# EndEffector.net
KiCad netlist of a schematic drawn in EAGLE
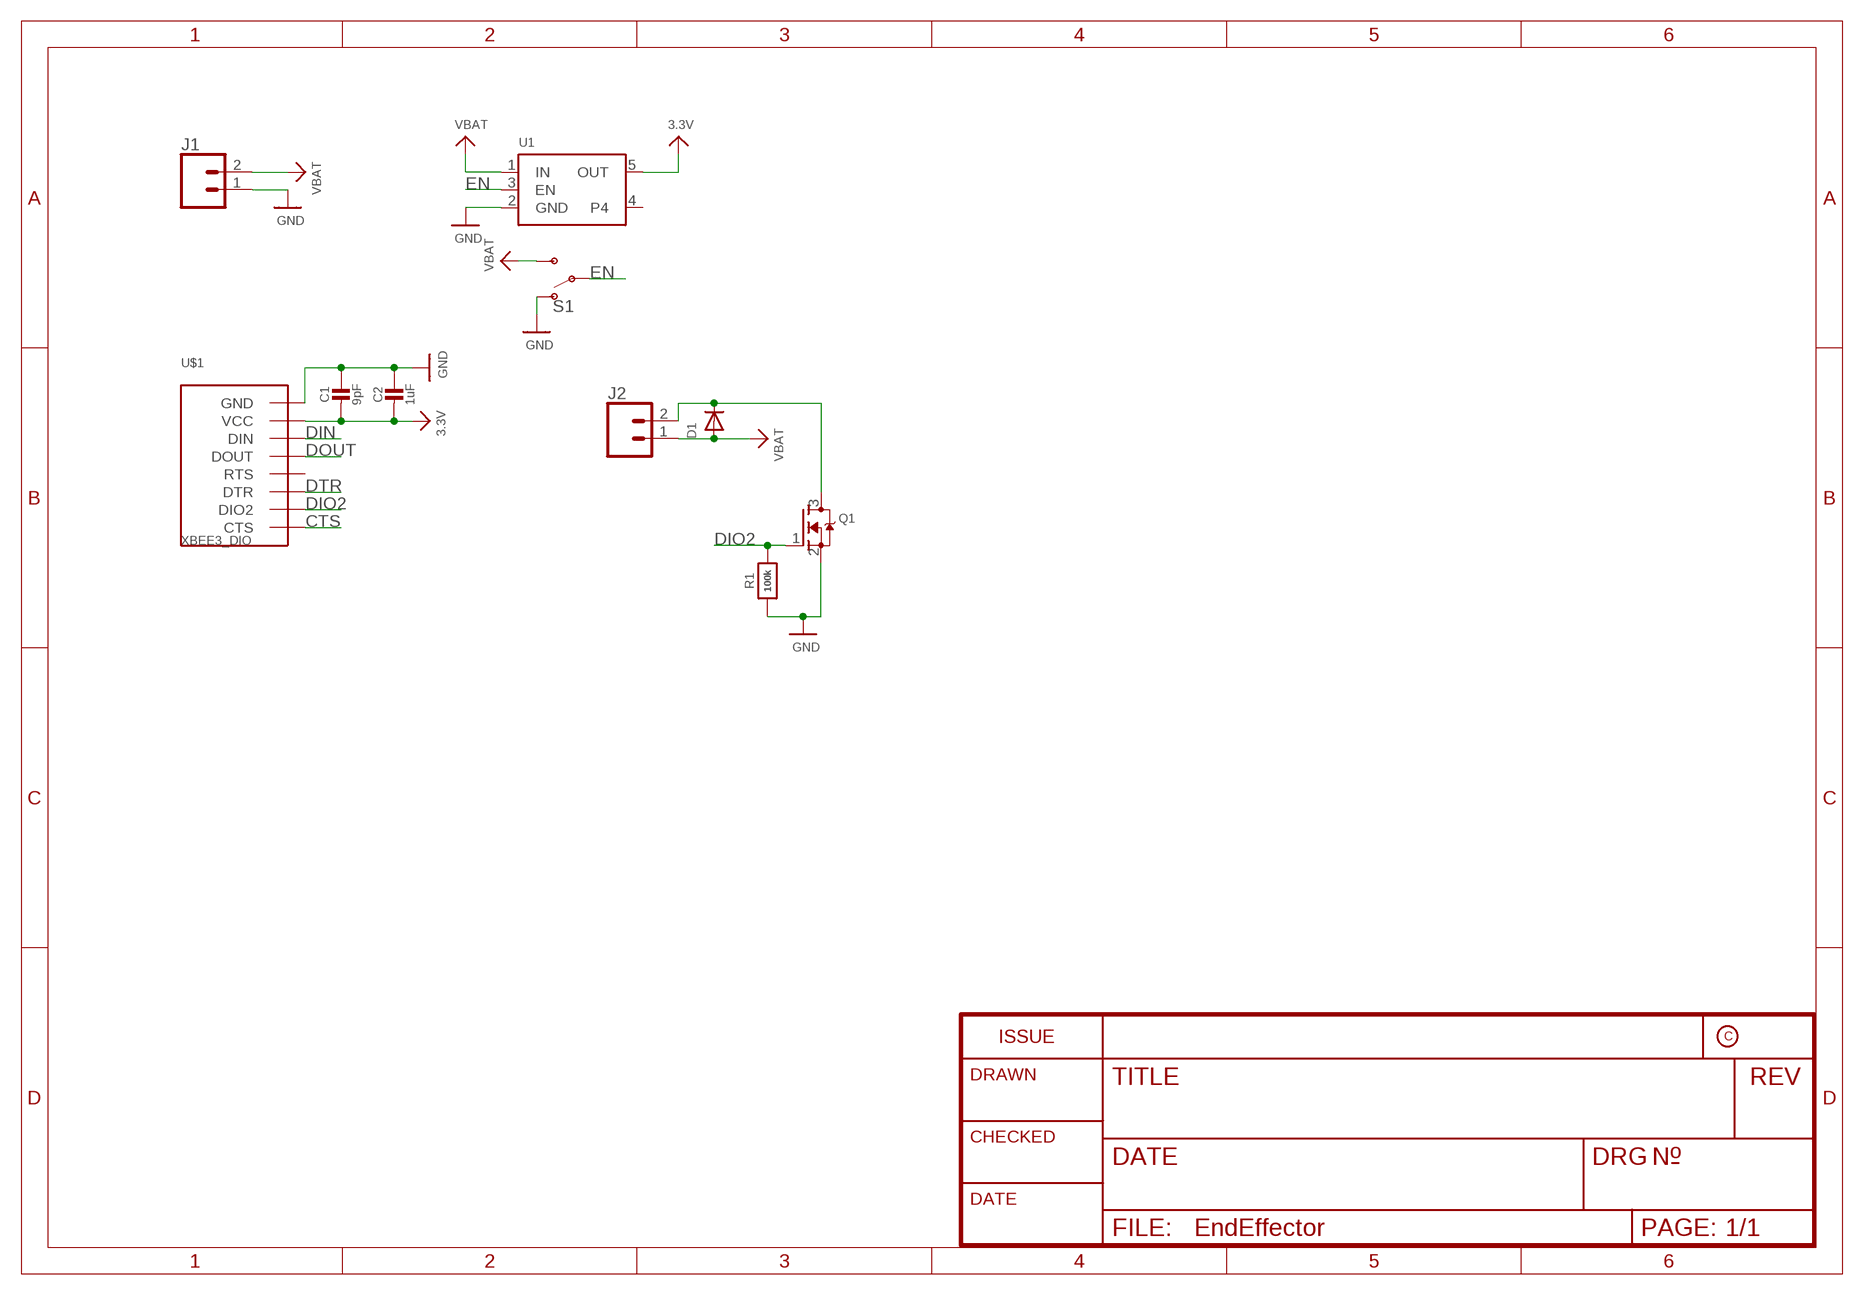
[diagram p0: schematic, sheet 1]

(export (version "E")
  (design (tool "Eeschema 10.0.6"))
  (components
    (comp (ref "C1")
      (value "9pF")
      (footprint "eagle-import:_0603")
      (libsource (lib "eagle-import") (part "CAP_CERAMIC_0603"))
    )
    (comp (ref "C2")
      (value "1uF")
      (footprint "eagle-import:_0603")
      (libsource (lib "eagle-import") (part "CAP_CERAMIC_0603"))
    )
    (comp (ref "D1")
      (value "DIODESOD-123")
      (footprint "eagle-import:SOD-123")
      (libsource (lib "eagle-import") (part "DIODESOD-123"))
    )
    (comp (ref "J1")
      (value "CONN_02JST-PTH-2-KIT")
      (footprint "eagle-import:JST-2-PTH-KIT")
      (libsource (lib "eagle-import") (part "CONN_02JST-PTH-2-KIT"))
    )
    (comp (ref "J2")
      (value "CONN_02")
      (footprint "eagle-import:1X02")
      (libsource (lib "eagle-import") (part "CONN_02"))
    )
    (comp (ref "Q1")
      (value "MOSFET-NREFLOW")
      (footprint "eagle-import:SOT23")
      (libsource (lib "eagle-import") (part "MOSFET-NREFLOW"))
    )
    (comp (ref "R1")
      (value "100k")
      (footprint "eagle-import:_0603")
      (libsource (lib "eagle-import") (part "RESISTOR_0603"))
    )
    (comp (ref "S1")
      (value "SWITCH-SPDT-SMD-AYZ0202")
      (footprint "eagle-import:SWITCH_DPDT_SMD_AYZ0202")
      (libsource (lib "eagle-import") (part "SWITCH-SPDT-SMD-AYZ0202"))
    )
    (comp (ref "U$1")
      (value "XBEE3_DIO")
      (footprint "eagle-import:XBEE3_MICRO")
      (libsource (lib "eagle-import") (part "XBEE3_DIO"))
    )
    (comp (ref "U1")
      (value "VREG_SOT23-5")
      (footprint "eagle-import:SOT23-5")
      (libsource (lib "eagle-import") (part "VREG_SOT23-5"))
    )
  )
  (nets
    (net (code "1") (name "/CTS") (class "Default")
      (node (ref "U$1") (pin "CTS/DIO7") (pinfunction "CTS_CTS/DIO7") (pintype "bidirectional"))
    )
    (net (code "2") (name "/DIN") (class "Default")
      (node (ref "U$1") (pin "DIN/CONFIG/DIO14") (pinfunction "DIN_DIN/CONFIG/DIO14") (pintype "bidirectional"))
    )
    (net (code "3") (name "/DIO2") (class "Default")
      (node (ref "Q1") (pin "1") (pinfunction "G_1") (pintype "bidirectional"))
      (node (ref "R1") (pin "2") (pinfunction "2_2") (pintype "passive"))
      (node (ref "U$1") (pin "AD2/DIO2") (pinfunction "DIO2_AD2/DIO2") (pintype "bidirectional"))
    )
    (net (code "4") (name "/DOUT") (class "Default")
      (node (ref "U$1") (pin "DOUT/DIO13") (pinfunction "DOUT_DOUT/DIO13") (pintype "bidirectional"))
    )
    (net (code "5") (name "/DTR") (class "Default")
      (node (ref "U$1") (pin "DTR/SLEEP_RQ/DIO8") (pinfunction "DTR_DTR/SLEEP_RQ/DIO8") (pintype "bidirectional"))
    )
    (net (code "6") (name "/EN") (class "Default")
      (node (ref "S1") (pin "2") (pinfunction "P_2") (pintype "passive"))
      (node (ref "U1") (pin "3") (pinfunction "EN_3") (pintype "input"))
    )
    (net (code "7") (name "3.3V") (class "Default")
      (node (ref "C1") (pin "2") (pinfunction "2_2") (pintype "passive"))
      (node (ref "C2") (pin "2") (pinfunction "2_2") (pintype "passive"))
      (node (ref "U$1") (pin "VCC") (pinfunction "VCC_VCC") (pintype "bidirectional"))
      (node (ref "U1") (pin "5") (pinfunction "OUT_5") (pintype "power_in"))
    )
    (net (code "8") (name "GND") (class "Default")
      (node (ref "C1") (pin "1") (pinfunction "1_1") (pintype "passive"))
      (node (ref "C2") (pin "1") (pinfunction "1_1") (pintype "passive"))
      (node (ref "J1") (pin "1") (pinfunction "1_1") (pintype "passive"))
      (node (ref "Q1") (pin "2") (pinfunction "S_2") (pintype "bidirectional"))
      (node (ref "R1") (pin "1") (pinfunction "1_1") (pintype "passive"))
      (node (ref "S1") (pin "1") (pinfunction "O_1") (pintype "passive"))
      (node (ref "U$1") (pin "GND1") (pinfunction "GND_GND1") (pintype "bidirectional"))
      (node (ref "U$1") (pin "GND2") (pinfunction "GND_GND2") (pintype "bidirectional"))
      (node (ref "U$1") (pin "GND3") (pinfunction "GND_GND3") (pintype "bidirectional"))
      (node (ref "U$1") (pin "GND4") (pinfunction "GND_GND4") (pintype "bidirectional"))
      (node (ref "U$1") (pin "GND5") (pinfunction "GND_GND5") (pintype "bidirectional"))
      (node (ref "U$1") (pin "GND6") (pinfunction "GND_GND6") (pintype "bidirectional"))
      (node (ref "U1") (pin "2") (pinfunction "GND_2") (pintype "power_in"))
    )
    (net (code "9") (name "Net-(Q1-D)") (class "Default")
      (node (ref "D1") (pin "C") (pinfunction "C_C") (pintype "passive"))
      (node (ref "J2") (pin "2") (pinfunction "2_2") (pintype "passive"))
      (node (ref "Q1") (pin "3") (pinfunction "D_3") (pintype "bidirectional"))
    )
    (net (code "10") (name "VBAT") (class "Default")
      (node (ref "D1") (pin "A") (pinfunction "A_A") (pintype "passive"))
      (node (ref "J1") (pin "2") (pinfunction "2_2") (pintype "passive"))
      (node (ref "J2") (pin "1") (pinfunction "1_1") (pintype "passive"))
      (node (ref "S1") (pin "3") (pinfunction "S_3") (pintype "passive"))
      (node (ref "U1") (pin "1") (pinfunction "IN_1") (pintype "power_in"))
    )
    (net (code "11") (name "unconnected-(U$1-RTS-PadRTS{slash}DIO6)") (class "Default")
      (node (ref "U$1") (pin "RTS/DIO6") (pinfunction "RTS_RTS/DIO6") (pintype "bidirectional"))
    )
    (net (code "12") (name "unconnected-(U1-P4-Pad4)") (class "Default")
      (node (ref "U1") (pin "4") (pinfunction "P4_4") (pintype "bidirectional"))
    )
  )
)
